# stm32f103c8t6.net
KiCad netlist of a schematic drawn in EasyEDA Pro
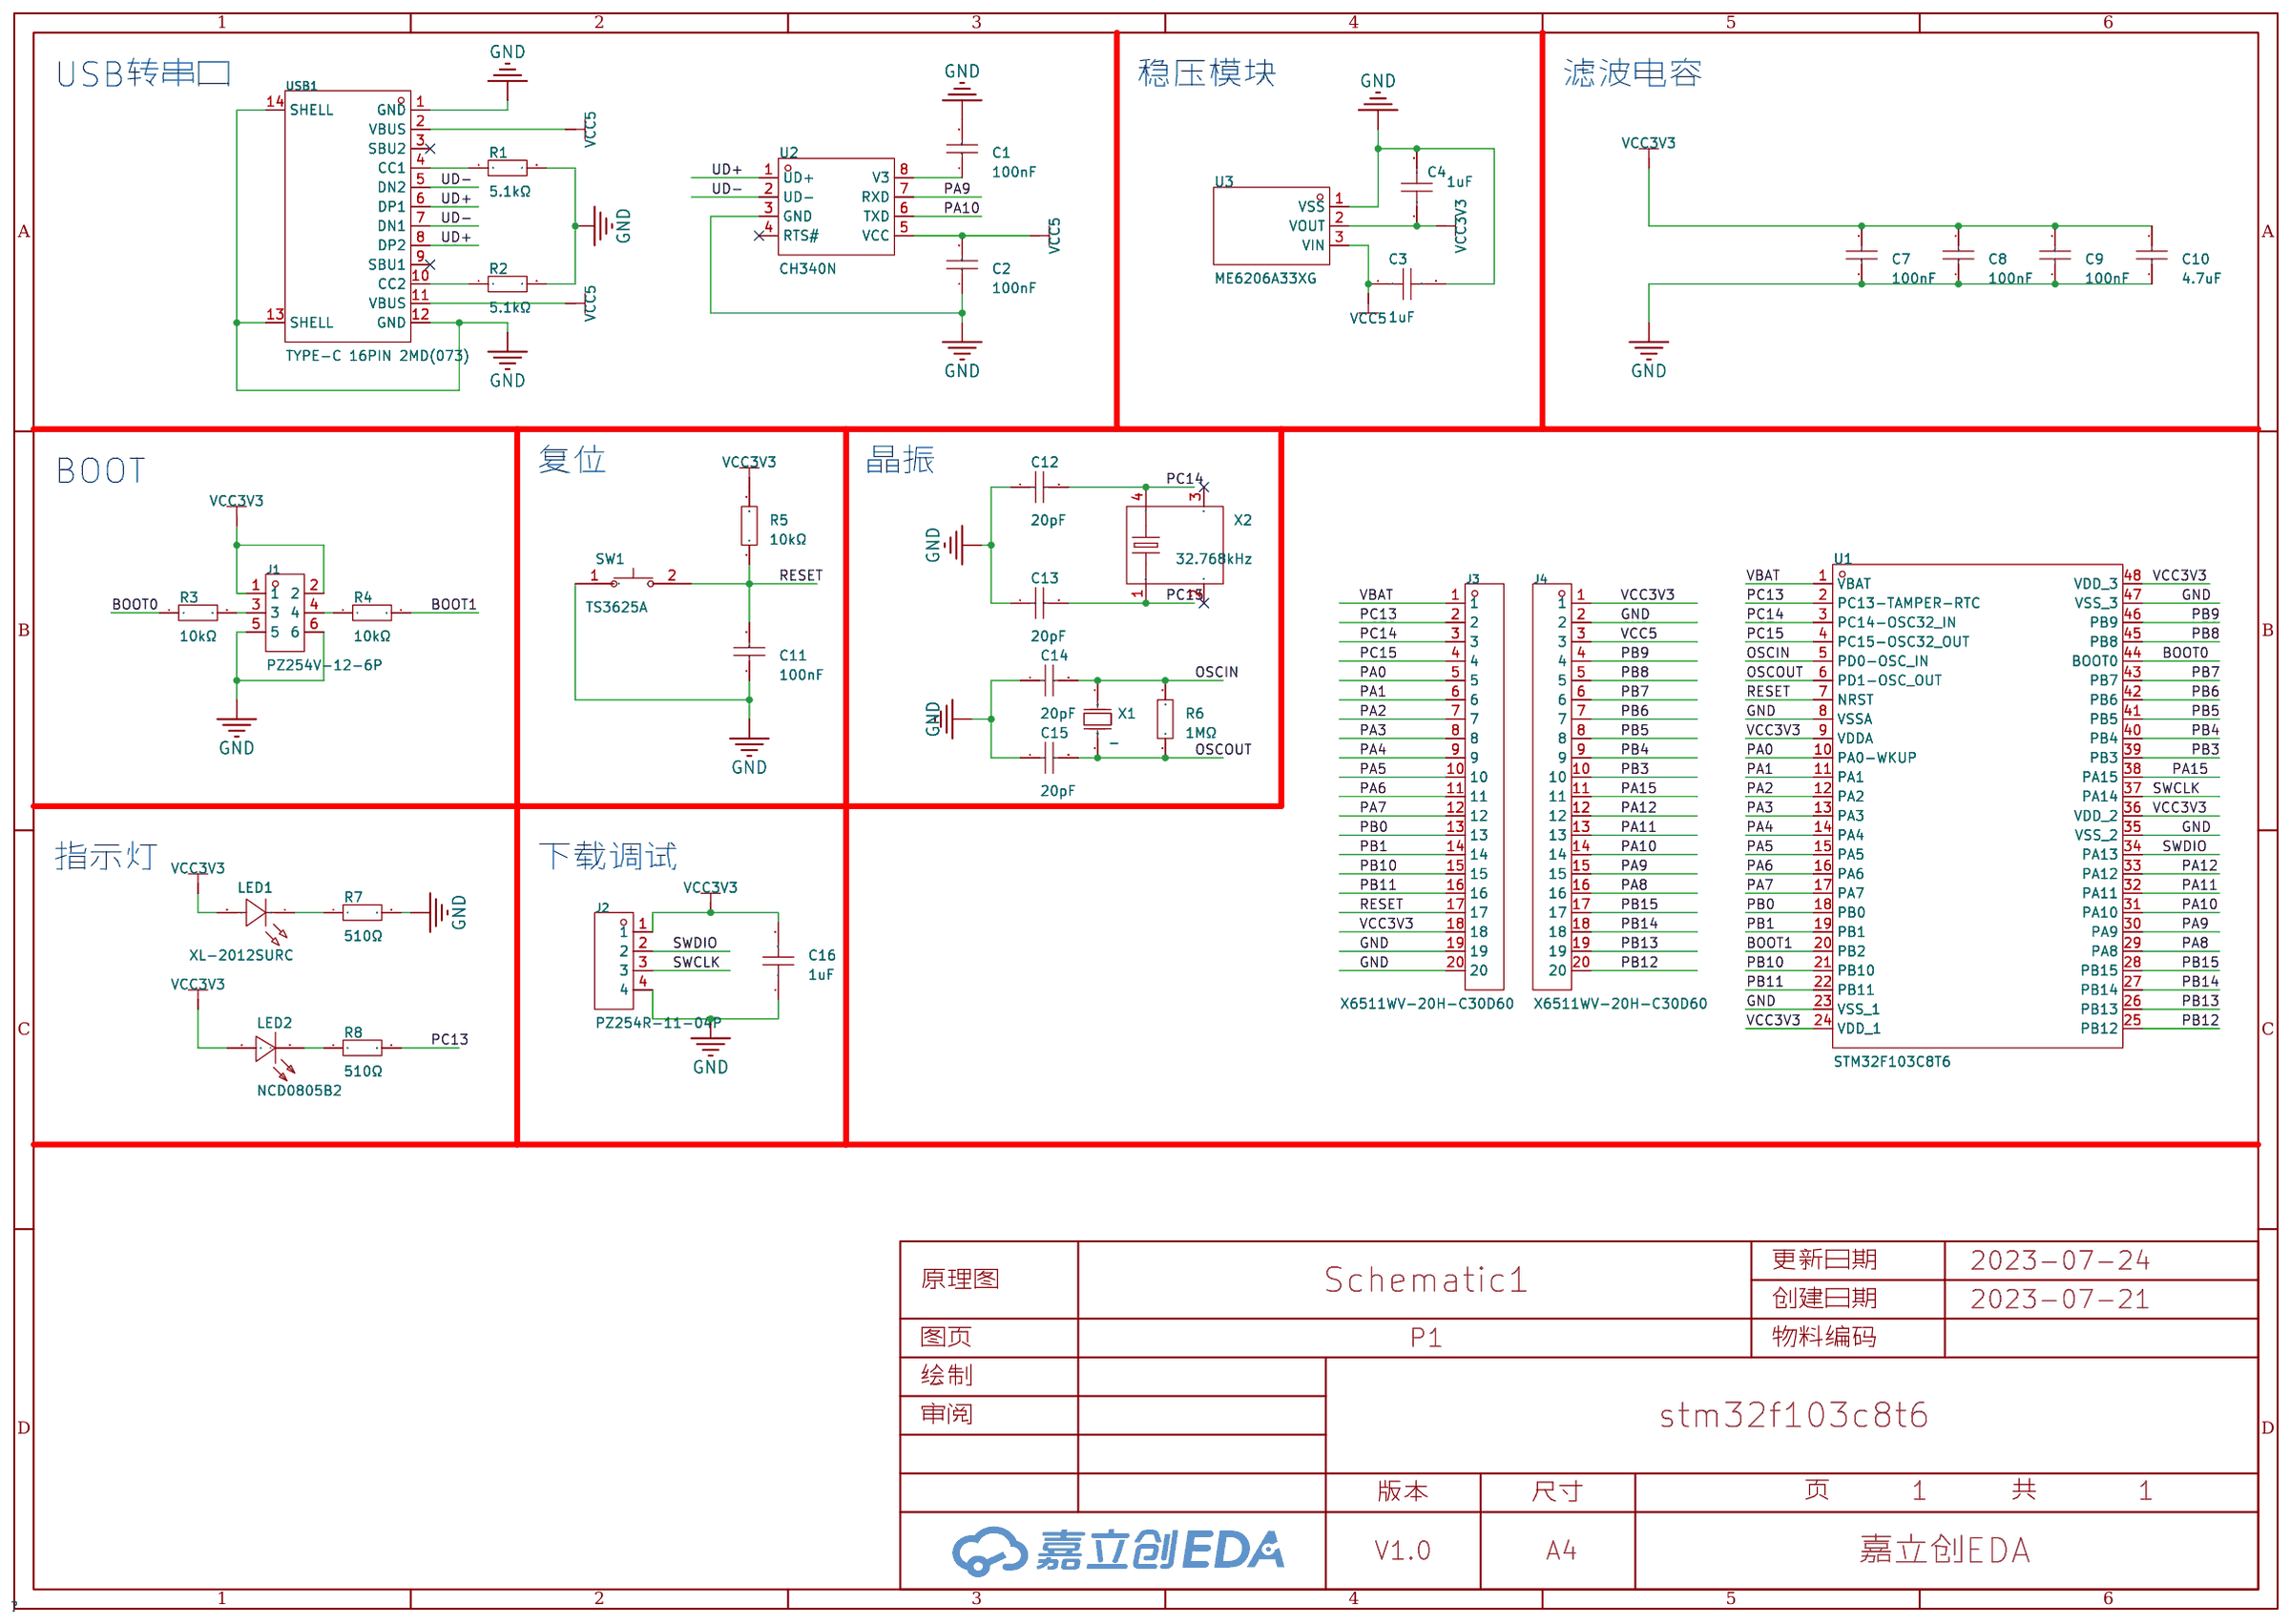
[diagram p0: schematic sheet]

(export (version "E")
  (design (tool "Eeschema 10.0.6"))
  (components
    (comp (ref "C1")
      (value "100nF")
      (footprint "easyedapro:C0603")
      (description "容值:100nF;精度:±10%;额定电压:50V;材质(温度系数):X7R;")
      (fields (field (name "Manufacturer Part") "0603B104K500NT") (field (name "Manufacturer") "FH(风华)"))
      (libsource (lib "easyedapro") (part "0603B104K500NT"))
    )
    (comp (ref "C2")
      (value "100nF")
      (footprint "easyedapro:C0603")
      (description "容值:100nF;精度:±10%;额定电压:50V;材质(温度系数):X7R;")
      (fields (field (name "Manufacturer Part") "0603B104K500NT") (field (name "Manufacturer") "FH(风华)"))
      (libsource (lib "easyedapro") (part "0603B104K500NT"))
    )
    (comp (ref "C3")
      (value "1uF")
      (footprint "easyedapro:C0603")
      (description "温度系数:X7R;精度:±10%;额定电压:50V;容值:1uF;")
      (fields (field (name "Manufacturer Part") "0603B105K500NT") (field (name "Manufacturer") "FH(风华)"))
      (libsource (lib "easyedapro") (part "0603B105K500NT"))
    )
    (comp (ref "C4")
      (value "1uF")
      (footprint "easyedapro:C0603")
      (description "温度系数:X7R;精度:±10%;额定电压:50V;容值:1uF;")
      (fields (field (name "Manufacturer Part") "0603B105K500NT") (field (name "Manufacturer") "FH(风华)"))
      (libsource (lib "easyedapro") (part "0603B105K500NT"))
    )
    (comp (ref "C7")
      (value "100nF")
      (footprint "easyedapro:C0603")
      (description "容值:100nF;精度:±10%;额定电压:50V;材质(温度系数):X7R;")
      (fields (field (name "Manufacturer Part") "0603B104K500NT") (field (name "Manufacturer") "FH(风华)"))
      (libsource (lib "easyedapro") (part "0603B104K500NT"))
    )
    (comp (ref "C8")
      (value "100nF")
      (footprint "easyedapro:C0603")
      (description "容值:100nF;精度:±10%;额定电压:50V;材质(温度系数):X7R;")
      (fields (field (name "Manufacturer Part") "0603B104K500NT") (field (name "Manufacturer") "FH(风华)"))
      (libsource (lib "easyedapro") (part "0603B104K500NT"))
    )
    (comp (ref "C9")
      (value "100nF")
      (footprint "easyedapro:C0603")
      (description "容值:100nF;精度:±10%;额定电压:50V;材质(温度系数):X7R;")
      (fields (field (name "Manufacturer Part") "0603B104K500NT") (field (name "Manufacturer") "FH(风华)"))
      (libsource (lib "easyedapro") (part "0603B104K500NT"))
    )
    (comp (ref "C10")
      (value "4.7uF")
      (footprint "easyedapro:C1206")
      (description "容值:4.7uF;精度:±10%;额定电压:50V;材质(温度系数):X7R;")
      (fields
        (field (name "Manufacturer Part") "CL10A475KO8NNNC")
        (field (name "Manufacturer") "SAMSUNG(三星)")
      )
      (libsource (lib "easyedapro") (part "1206B475K500NT"))
    )
    (comp (ref "C11")
      (value "100nF")
      (footprint "easyedapro:C0603")
      (description "容值:100nF;精度:±10%;额定电压:50V;材质(温度系数):X7R;")
      (fields (field (name "Manufacturer Part") "0603B104K500NT") (field (name "Manufacturer") "FH(风华)"))
      (libsource (lib "easyedapro") (part "0603B104K500NT"))
    )
    (comp (ref "C12")
      (value "20pF")
      (footprint "easyedapro:C0603")
      (description "容值:20pF;精度:±5%;额定电压:50V;材质(温度系数):NP0;")
      (fields
        (field (name "Manufacturer Part") "CC0603JRNPO9BN200")
        (field (name "Manufacturer") "YAGEO(国巨)")
      )
      (libsource (lib "easyedapro") (part "CC0603JRNPO9BN200"))
    )
    (comp (ref "C13")
      (value "20pF")
      (footprint "easyedapro:C0603")
      (description "容值:20pF;精度:±5%;额定电压:50V;材质(温度系数):NP0;")
      (fields
        (field (name "Manufacturer Part") "CC0603JRNPO9BN200")
        (field (name "Manufacturer") "YAGEO(国巨)")
      )
      (libsource (lib "easyedapro") (part "CC0603JRNPO9BN200"))
    )
    (comp (ref "C14")
      (value "20pF")
      (footprint "easyedapro:C0603")
      (description "容值:20pF;精度:±5%;额定电压:50V;材质(温度系数):NP0;")
      (fields
        (field (name "Manufacturer Part") "CC0603JRNPO9BN200")
        (field (name "Manufacturer") "YAGEO(国巨)")
      )
      (libsource (lib "easyedapro") (part "CC0603JRNPO9BN200"))
    )
    (comp (ref "C15")
      (value "20pF")
      (footprint "easyedapro:C0603")
      (description "容值:20pF;精度:±5%;额定电压:50V;材质(温度系数):NP0;")
      (fields
        (field (name "Manufacturer Part") "CC0603JRNPO9BN200")
        (field (name "Manufacturer") "YAGEO(国巨)")
      )
      (libsource (lib "easyedapro") (part "CC0603JRNPO9BN200"))
    )
    (comp (ref "C16")
      (value "1uF")
      (footprint "easyedapro:C0603")
      (description "温度系数:X7R;精度:±10%;额定电压:50V;容值:1uF;")
      (fields (field (name "Manufacturer Part") "0603B105K500NT") (field (name "Manufacturer") "FH(风华)"))
      (libsource (lib "easyedapro") (part "0603B105K500NT"))
    )
    (comp (ref "J1")
      (value "PZ254V-12-6P")
      (footprint "easyedapro:HDR-TH_6P-P2.54-V-M-R2-C3-S2.54")
      (fields (field (name "Manufacturer") "XFCN(兴飞)"))
      (libsource (lib "easyedapro") (part "PZ254V-12-6P"))
    )
    (comp (ref "J2")
      (value "PZ254R-11-04P")
      (footprint "easyedapro:HDR-TH_4P-P2.54-H-M-W10.4")
      (fields (field (name "Manufacturer") "XFCN(兴飞)"))
      (libsource (lib "easyedapro") (part "PZ254R-11-04P"))
    )
    (comp (ref "J3")
      (value "X6511WV-20H-C30D60")
      (footprint "easyedapro:HDR-TH_20P-P2.54-V-M")
      (fields (field (name "Manufacturer") "XKB Connectivity(中国星坤)"))
      (libsource (lib "easyedapro") (part "X6511WV-20H-C30D60"))
    )
    (comp (ref "J4")
      (value "X6511WV-20H-C30D60")
      (footprint "easyedapro:HDR-TH_20P-P2.54-V-M")
      (fields (field (name "Manufacturer") "XKB Connectivity(中国星坤)"))
      (libsource (lib "easyedapro") (part "X6511WV-20H-C30D60"))
    )
    (comp (ref "LED1")
      (value "XL-2012SURC")
      (footprint "easyedapro:LED0805-RD_RED")
      (description "发光颜色:红灯;主波长:617nm~621nm;色温:-;功率:55mW;安装方式:正贴;")
      (fields (field (name "Manufacturer") "XINGLIGHT(成兴光)"))
      (libsource (lib "easyedapro") (part "XL-2012SURC"))
    )
    (comp (ref "LED2")
      (value "NCD0805B2")
      (footprint "easyedapro:LED0805-R-RD")
      (description "发光颜色:蓝灯;")
      (fields (field (name "Manufacturer") "国星光电"))
      (libsource (lib "easyedapro") (part "FC-A2012BK-470H2"))
    )
    (comp (ref "R1")
      (value "5.1kΩ")
      (footprint "easyedapro:R0603")
      (description "电阻类型:厚膜电阻;阻值:5.1kΩ;精度:±1%;功率:100mW;")
      (fields
        (field (name "Manufacturer Part") "0603WAF5101T5E")
        (field (name "Manufacturer") "UNI-ROYAL(厚声)")
      )
      (libsource (lib "easyedapro") (part "0603WAF5101T5E"))
    )
    (comp (ref "R2")
      (value "5.1kΩ")
      (footprint "easyedapro:R0603")
      (description "电阻类型:厚膜电阻;阻值:5.1kΩ;精度:±1%;功率:100mW;")
      (fields
        (field (name "Manufacturer Part") "0603WAF5101T5E")
        (field (name "Manufacturer") "UNI-ROYAL(厚声)")
      )
      (libsource (lib "easyedapro") (part "0603WAF5101T5E"))
    )
    (comp (ref "R3")
      (value "10kΩ")
      (footprint "easyedapro:R0603")
      (description "电阻类型:厚膜电阻;阻值:10kΩ;精度:±1%;功率:100mW;")
      (fields
        (field (name "Manufacturer Part") "0603WAF1002T5E")
        (field (name "Manufacturer") "UNI-ROYAL(厚声)")
      )
      (libsource (lib "easyedapro") (part "0603WAF1002T5E"))
    )
    (comp (ref "R4")
      (value "10kΩ")
      (footprint "easyedapro:R0603")
      (description "电阻类型:厚膜电阻;阻值:10kΩ;精度:±1%;功率:100mW;")
      (fields
        (field (name "Manufacturer Part") "0603WAF1002T5E")
        (field (name "Manufacturer") "UNI-ROYAL(厚声)")
      )
      (libsource (lib "easyedapro") (part "0603WAF1002T5E"))
    )
    (comp (ref "R5")
      (value "10kΩ")
      (footprint "easyedapro:R0603")
      (description "电阻类型:厚膜电阻;阻值:10kΩ;精度:±1%;功率:100mW;")
      (fields
        (field (name "Manufacturer Part") "0603WAF1002T5E")
        (field (name "Manufacturer") "UNI-ROYAL(厚声)")
      )
      (libsource (lib "easyedapro") (part "0603WAF1002T5E"))
    )
    (comp (ref "R6")
      (value "1MΩ")
      (footprint "easyedapro:R0603")
      (description "电阻类型:厚膜电阻;阻值:1MΩ;精度:±1%;功率:100mW;")
      (fields
        (field (name "Manufacturer Part") "0603WAF1004T5E")
        (field (name "Manufacturer") "UNI-ROYAL(厚声)")
      )
      (libsource (lib "easyedapro") (part "0603WAF1004T5E"))
    )
    (comp (ref "R7")
      (value "510Ω")
      (footprint "easyedapro:R0603")
      (description "电阻类型:厚膜电阻;阻值:510Ω;精度:±1%;功率:100mW;")
      (fields
        (field (name "Manufacturer Part") "0603WAF5100T5E")
        (field (name "Manufacturer") "UNI-ROYAL(厚声)")
      )
      (libsource (lib "easyedapro") (part "0603WAF5100T5E"))
    )
    (comp (ref "R8")
      (value "510Ω")
      (footprint "easyedapro:R0603")
      (description "电阻类型:厚膜电阻;阻值:510Ω;精度:±1%;功率:100mW;")
      (fields
        (field (name "Manufacturer Part") "0603WAF5100T5E")
        (field (name "Manufacturer") "UNI-ROYAL(厚声)")
      )
      (libsource (lib "easyedapro") (part "0603WAF5100T5E"))
    )
    (comp (ref "SW1")
      (value "TS3625A")
      (footprint "easyedapro:KEY-SMD_L6.0-W3.5-LS8.4")
      (description "触点电流:50mA;额定电压(DC):12V;电路结构:单刀单掷;安装方式:立贴;带灯:-;作用力:250gf@±50gf;机械寿命:-;")
      (fields (field (name "Manufacturer") "SHOU HAN(首韩)"))
      (libsource (lib "easyedapro") (part "TS3625A"))
    )
    (comp (ref "U1")
      (value "STM32F103C8T6")
      (footprint "easyedapro:LQFP-48_L7.0-W7.0-P0.50-LS9.0-BL")
      (description "CPU内核:ARM Cortex-M3;CPU最大主频:72MHz;程序存储容量:64KB;程序存储器类型:FLASH;RAM总容量:20KB;GPIO端口数量:37;")
      (fields (field (name "Manufacturer") "ST(意法半导体)"))
      (libsource (lib "easyedapro") (part "STM32F103C8T6"))
    )
    (comp (ref "U2")
      (value "CH340N")
      (footprint "easyedapro:SOP-8_L4.9-W3.9-P1.27-LS6.0-BL")
      (fields (field (name "Manufacturer") "WCH(南京沁恒)"))
      (libsource (lib "easyedapro") (part "CH340N_C2977777"))
    )
    (comp (ref "U3")
      (value "ME6206A33XG")
      (footprint "easyedapro:SOT-23-3_L2.9-W1.6-P1.90-LS2.8-BR")
      (description "输出类型:固定;输出极性:正;最大输入电压:6V;输出电压:3.3V;输出电流:300mA;电源纹波抑制比(PSRR):50dB@(1kHz);")
      (fields (field (name "Manufacturer") "MICRONE(南京微盟)"))
      (libsource (lib "easyedapro") (part "ME6206A33XG"))
    )
    (comp (ref "USB1")
      (value "TYPE-C 16PIN 2MD(073)")
      (footprint "easyedapro:USB-C-SMD_TYPE-C-6PIN-2MD-073")
      (description "连接器类型:Type-C;标准:-;公母:母座;触点数量:16;端口数量:1;安装方式:卧贴;额定电流 - 电源:5A;工作温度范围:-25°C~+85°C;")
      (fields (field (name "Manufacturer") "SHOU HAN(首韩)"))
      (libsource (lib "easyedapro") (part "TYPE-C 16PIN 2MD(073)"))
    )
    (comp (ref "X1")
      (value "-")
      (footprint "easyedapro:CRYSTAL-SMD_L11.5-W4.8-LS12.7")
      (description "频率:8MHz;频率公差:±20ppm;负载电容:20pF;")
      (fields
        (field (name "Manufacturer Part") "XIHCELNANF-8MHZ")
        (field (name "Manufacturer") "TAITIEN(泰艺电子)")
      )
      (libsource (lib "easyedapro") (part "X49SM8MSD2SC"))
    )
    (comp (ref "X2")
      (value "32.768kHz")
      (footprint "easyedapro:MC-306_4P-L8.0-W3.2-P5.5-BL")
      (description "频率:32.768kHz;频率公差:±20ppm;负载电容:6pF;")
      (fields (field (name "Manufacturer Part") "Q13MC3062000600") (field (name "Manufacturer") "EPSON(爱普生)"))
      (libsource (lib "easyedapro") (part "MC-306 32.768kHz 6.0pF 20ppm"))
    )
  )
  (nets
    (net (code "1") (name "/BOOT0") (class "Default")
      (node (ref "R3") (pin "1") (pinfunction "1_1") (pintype "input"))
      (node (ref "U1") (pin "44") (pinfunction "BOOT0_44") (pintype "input"))
    )
    (net (code "2") (name "/BOOT1") (class "Default")
      (node (ref "R4") (pin "2") (pinfunction "2_2") (pintype "input"))
      (node (ref "U1") (pin "20") (pinfunction "PB2_20") (pintype "input"))
    )
    (net (code "3") (name "/OSCIN") (class "Default")
      (node (ref "C14") (pin "2") (pinfunction "2_2") (pintype "input"))
      (node (ref "R6") (pin "2") (pinfunction "2_2") (pintype "input"))
      (node (ref "U1") (pin "5") (pinfunction "PD0-OSC_IN_5") (pintype "input"))
      (node (ref "X1") (pin "1") (pinfunction "OSC1_1") (pintype "input"))
    )
    (net (code "4") (name "/OSCOUT") (class "Default")
      (node (ref "C15") (pin "2") (pinfunction "2_2") (pintype "input"))
      (node (ref "R6") (pin "1") (pinfunction "1_1") (pintype "input"))
      (node (ref "U1") (pin "6") (pinfunction "PD1-OSC_OUT_6") (pintype "input"))
      (node (ref "X1") (pin "2") (pinfunction "OSC2_2") (pintype "input"))
    )
    (net (code "5") (name "/PA0") (class "Default")
      (node (ref "J3") (pin "5") (pinfunction "5_5") (pintype "input"))
      (node (ref "U1") (pin "10") (pinfunction "PA0-WKUP_10") (pintype "input"))
    )
    (net (code "6") (name "/PA1") (class "Default")
      (node (ref "J3") (pin "6") (pinfunction "6_6") (pintype "input"))
      (node (ref "U1") (pin "11") (pinfunction "PA1_11") (pintype "input"))
    )
    (net (code "7") (name "/PA2") (class "Default")
      (node (ref "J3") (pin "7") (pinfunction "7_7") (pintype "input"))
      (node (ref "U1") (pin "12") (pinfunction "PA2_12") (pintype "input"))
    )
    (net (code "8") (name "/PA3") (class "Default")
      (node (ref "J3") (pin "8") (pinfunction "8_8") (pintype "input"))
      (node (ref "U1") (pin "13") (pinfunction "PA3_13") (pintype "input"))
    )
    (net (code "9") (name "/PA4") (class "Default")
      (node (ref "J3") (pin "9") (pinfunction "9_9") (pintype "input"))
      (node (ref "U1") (pin "14") (pinfunction "PA4_14") (pintype "input"))
    )
    (net (code "10") (name "/PA5") (class "Default")
      (node (ref "J3") (pin "10") (pinfunction "10_10") (pintype "input"))
      (node (ref "U1") (pin "15") (pinfunction "PA5_15") (pintype "input"))
    )
    (net (code "11") (name "/PA6") (class "Default")
      (node (ref "J3") (pin "11") (pinfunction "11_11") (pintype "input"))
      (node (ref "U1") (pin "16") (pinfunction "PA6_16") (pintype "input"))
    )
    (net (code "12") (name "/PA7") (class "Default")
      (node (ref "J3") (pin "12") (pinfunction "12_12") (pintype "input"))
      (node (ref "U1") (pin "17") (pinfunction "PA7_17") (pintype "input"))
    )
    (net (code "13") (name "/PA8") (class "Default")
      (node (ref "J4") (pin "16") (pinfunction "16_16") (pintype "input"))
      (node (ref "U1") (pin "29") (pinfunction "PA8_29") (pintype "input"))
    )
    (net (code "14") (name "/PA9") (class "Default")
      (node (ref "J4") (pin "15") (pinfunction "15_15") (pintype "input"))
      (node (ref "U1") (pin "30") (pinfunction "PA9_30") (pintype "input"))
      (node (ref "U2") (pin "7") (pinfunction "RXD_7") (pintype "input"))
    )
    (net (code "15") (name "/PA10") (class "Default")
      (node (ref "J4") (pin "14") (pinfunction "14_14") (pintype "input"))
      (node (ref "U1") (pin "31") (pinfunction "PA10_31") (pintype "input"))
      (node (ref "U2") (pin "6") (pinfunction "TXD_6") (pintype "input"))
    )
    (net (code "16") (name "/PA11") (class "Default")
      (node (ref "J4") (pin "13") (pinfunction "13_13") (pintype "input"))
      (node (ref "U1") (pin "32") (pinfunction "PA11_32") (pintype "input"))
    )
    (net (code "17") (name "/PA12") (class "Default")
      (node (ref "J4") (pin "12") (pinfunction "12_12") (pintype "input"))
      (node (ref "U1") (pin "33") (pinfunction "PA12_33") (pintype "input"))
    )
    (net (code "18") (name "/PA15") (class "Default")
      (node (ref "J4") (pin "11") (pinfunction "11_11") (pintype "input"))
      (node (ref "U1") (pin "38") (pinfunction "PA15_38") (pintype "input"))
    )
    (net (code "19") (name "/PB0") (class "Default")
      (node (ref "J3") (pin "13") (pinfunction "13_13") (pintype "input"))
      (node (ref "U1") (pin "18") (pinfunction "PB0_18") (pintype "input"))
    )
    (net (code "20") (name "/PB1") (class "Default")
      (node (ref "J3") (pin "14") (pinfunction "14_14") (pintype "input"))
      (node (ref "U1") (pin "19") (pinfunction "PB1_19") (pintype "input"))
    )
    (net (code "21") (name "/PB3") (class "Default")
      (node (ref "J4") (pin "10") (pinfunction "10_10") (pintype "input"))
      (node (ref "U1") (pin "39") (pinfunction "PB3_39") (pintype "input"))
    )
    (net (code "22") (name "/PB4") (class "Default")
      (node (ref "J4") (pin "9") (pinfunction "9_9") (pintype "input"))
      (node (ref "U1") (pin "40") (pinfunction "PB4_40") (pintype "input"))
    )
    (net (code "23") (name "/PB5") (class "Default")
      (node (ref "J4") (pin "8") (pinfunction "8_8") (pintype "input"))
      (node (ref "U1") (pin "41") (pinfunction "PB5_41") (pintype "input"))
    )
    (net (code "24") (name "/PB6") (class "Default")
      (node (ref "J4") (pin "7") (pinfunction "7_7") (pintype "input"))
      (node (ref "U1") (pin "42") (pinfunction "PB6_42") (pintype "input"))
    )
    (net (code "25") (name "/PB7") (class "Default")
      (node (ref "J4") (pin "6") (pinfunction "6_6") (pintype "input"))
      (node (ref "U1") (pin "43") (pinfunction "PB7_43") (pintype "input"))
    )
    (net (code "26") (name "/PB8") (class "Default")
      (node (ref "J4") (pin "5") (pinfunction "5_5") (pintype "input"))
      (node (ref "U1") (pin "45") (pinfunction "PB8_45") (pintype "input"))
    )
    (net (code "27") (name "/PB9") (class "Default")
      (node (ref "J4") (pin "4") (pinfunction "4_4") (pintype "input"))
      (node (ref "U1") (pin "46") (pinfunction "PB9_46") (pintype "input"))
    )
    (net (code "28") (name "/PB10") (class "Default")
      (node (ref "J3") (pin "15") (pinfunction "15_15") (pintype "input"))
      (node (ref "U1") (pin "21") (pinfunction "PB10_21") (pintype "input"))
    )
    (net (code "29") (name "/PB11") (class "Default")
      (node (ref "J3") (pin "16") (pinfunction "16_16") (pintype "input"))
      (node (ref "U1") (pin "22") (pinfunction "PB11_22") (pintype "input"))
    )
    (net (code "30") (name "/PB12") (class "Default")
      (node (ref "J4") (pin "20") (pinfunction "20_20") (pintype "input"))
      (node (ref "U1") (pin "25") (pinfunction "PB12_25") (pintype "input"))
    )
    (net (code "31") (name "/PB13") (class "Default")
      (node (ref "J4") (pin "19") (pinfunction "19_19") (pintype "input"))
      (node (ref "U1") (pin "26") (pinfunction "PB13_26") (pintype "input"))
    )
    (net (code "32") (name "/PB14") (class "Default")
      (node (ref "J4") (pin "18") (pinfunction "18_18") (pintype "input"))
      (node (ref "U1") (pin "27") (pinfunction "PB14_27") (pintype "input"))
    )
    (net (code "33") (name "/PB15") (class "Default")
      (node (ref "J4") (pin "17") (pinfunction "17_17") (pintype "input"))
      (node (ref "U1") (pin "28") (pinfunction "PB15_28") (pintype "input"))
    )
    (net (code "34") (name "/PC13") (class "Default")
      (node (ref "J3") (pin "2") (pinfunction "2_2") (pintype "input"))
      (node (ref "R8") (pin "2") (pinfunction "2_2") (pintype "input"))
      (node (ref "U1") (pin "2") (pinfunction "PC13-TAMPER-RTC_2") (pintype "input"))
    )
    (net (code "35") (name "/PC14") (class "Default")
      (node (ref "C12") (pin "2") (pinfunction "2_2") (pintype "input"))
      (node (ref "J3") (pin "3") (pinfunction "3_3") (pintype "input"))
      (node (ref "U1") (pin "3") (pinfunction "PC14-OSC32_IN_3") (pintype "input"))
      (node (ref "X2") (pin "4") (pinfunction "4_4") (pintype "input"))
    )
    (net (code "36") (name "/PC15") (class "Default")
      (node (ref "C13") (pin "2") (pinfunction "2_2") (pintype "input"))
      (node (ref "J3") (pin "4") (pinfunction "4_4") (pintype "input"))
      (node (ref "U1") (pin "4") (pinfunction "PC15-OSC32_OUT_4") (pintype "input"))
      (node (ref "X2") (pin "1") (pinfunction "1_1") (pintype "input"))
    )
    (net (code "37") (name "/RESET") (class "Default")
      (node (ref "C11") (pin "2") (pinfunction "2_2") (pintype "input"))
      (node (ref "J3") (pin "17") (pinfunction "17_17") (pintype "input"))
      (node (ref "R5") (pin "1") (pinfunction "1_1") (pintype "input"))
      (node (ref "SW1") (pin "2") (pinfunction "2_2") (pintype "input"))
      (node (ref "U1") (pin "7") (pinfunction "NRST_7") (pintype "input"))
    )
    (net (code "38") (name "/SWCLK") (class "Default")
      (node (ref "J2") (pin "3") (pinfunction "3_3") (pintype "input"))
      (node (ref "U1") (pin "37") (pinfunction "PA14_37") (pintype "input"))
    )
    (net (code "39") (name "/SWDIO") (class "Default")
      (node (ref "J2") (pin "2") (pinfunction "2_2") (pintype "input"))
      (node (ref "U1") (pin "34") (pinfunction "PA13_34") (pintype "input"))
    )
    (net (code "40") (name "/UD+") (class "Default")
      (node (ref "U2") (pin "1") (pinfunction "UD+_1") (pintype "input"))
      (node (ref "USB1") (pin "6") (pinfunction "DP1_6") (pintype "input"))
      (node (ref "USB1") (pin "8") (pinfunction "DP2_8") (pintype "input"))
    )
    (net (code "41") (name "/UD-") (class "Default")
      (node (ref "U2") (pin "2") (pinfunction "UD-_2") (pintype "input"))
      (node (ref "USB1") (pin "5") (pinfunction "DN2_5") (pintype "input"))
      (node (ref "USB1") (pin "7") (pinfunction "DN1_7") (pintype "input"))
    )
    (net (code "42") (name "/VBAT") (class "Default")
      (node (ref "J3") (pin "1") (pinfunction "1_1") (pintype "input"))
      (node (ref "U1") (pin "1") (pinfunction "VBAT_1") (pintype "input"))
    )
    (net (code "43") (name "GND") (class "Default")
      (node (ref "C1") (pin "2") (pinfunction "2_2") (pintype "input"))
      (node (ref "C10") (pin "1") (pinfunction "1_1") (pintype "input"))
      (node (ref "C11") (pin "1") (pinfunction "1_1") (pintype "input"))
      (node (ref "C12") (pin "1") (pinfunction "1_1") (pintype "input"))
      (node (ref "C13") (pin "1") (pinfunction "1_1") (pintype "input"))
      (node (ref "C14") (pin "1") (pinfunction "1_1") (pintype "input"))
      (node (ref "C15") (pin "1") (pinfunction "1_1") (pintype "input"))
      (node (ref "C16") (pin "1") (pinfunction "1_1") (pintype "input"))
      (node (ref "C2") (pin "1") (pinfunction "1_1") (pintype "input"))
      (node (ref "C3") (pin "2") (pinfunction "2_2") (pintype "input"))
      (node (ref "C4") (pin "2") (pinfunction "2_2") (pintype "input"))
      (node (ref "C7") (pin "1") (pinfunction "1_1") (pintype "input"))
      (node (ref "C8") (pin "1") (pinfunction "1_1") (pintype "input"))
      (node (ref "C9") (pin "1") (pinfunction "1_1") (pintype "input"))
      (node (ref "J1") (pin "5") (pinfunction "5_5") (pintype "input"))
      (node (ref "J1") (pin "6") (pinfunction "6_6") (pintype "input"))
      (node (ref "J2") (pin "4") (pinfunction "4_4") (pintype "input"))
      (node (ref "J3") (pin "19") (pinfunction "19_19") (pintype "input"))
      (node (ref "J3") (pin "20") (pinfunction "20_20") (pintype "input"))
      (node (ref "J4") (pin "2") (pinfunction "2_2") (pintype "input"))
      (node (ref "R1") (pin "2") (pinfunction "2_2") (pintype "input"))
      (node (ref "R2") (pin "2") (pinfunction "2_2") (pintype "input"))
      (node (ref "R7") (pin "2") (pinfunction "2_2") (pintype "input"))
      (node (ref "SW1") (pin "1") (pinfunction "1_1") (pintype "input"))
      (node (ref "U1") (pin "23") (pinfunction "VSS_1_23") (pintype "input"))
      (node (ref "U1") (pin "35") (pinfunction "VSS_2_35") (pintype "input"))
      (node (ref "U1") (pin "47") (pinfunction "VSS_3_47") (pintype "input"))
      (node (ref "U1") (pin "8") (pinfunction "VSSA_8") (pintype "input"))
      (node (ref "U2") (pin "3") (pinfunction "GND_3") (pintype "input"))
      (node (ref "U3") (pin "1") (pinfunction "VSS_1") (pintype "input"))
      (node (ref "USB1") (pin "1") (pinfunction "GND_1") (pintype "input"))
      (node (ref "USB1") (pin "12") (pinfunction "GND_12") (pintype "input"))
      (node (ref "USB1") (pin "13") (pinfunction "SHELL_13") (pintype "input"))
      (node (ref "USB1") (pin "14") (pinfunction "SHELL_14") (pintype "input"))
    )
    (net (code "44") (name "Net-(J1-Pad3)") (class "Default")
      (node (ref "J1") (pin "3") (pinfunction "3_3") (pintype "input"))
      (node (ref "R3") (pin "2") (pinfunction "2_2") (pintype "input"))
    )
    (net (code "45") (name "Net-(J1-Pad4)") (class "Default")
      (node (ref "J1") (pin "4") (pinfunction "4_4") (pintype "input"))
      (node (ref "R4") (pin "1") (pinfunction "1_1") (pintype "input"))
    )
    (net (code "46") (name "Net-(LED1-K)") (class "Default")
      (node (ref "LED1") (pin "1") (pinfunction "K_1") (pintype "input"))
      (node (ref "R7") (pin "1") (pinfunction "1_1") (pintype "input"))
    )
    (net (code "47") (name "Net-(LED2--)") (class "Default")
      (node (ref "LED2") (pin "2") (pinfunction "-_2") (pintype "input"))
      (node (ref "R8") (pin "1") (pinfunction "1_1") (pintype "input"))
    )
    (net (code "48") (name "Net-(U2-V3)") (class "Default")
      (node (ref "C1") (pin "1") (pinfunction "1_1") (pintype "input"))
      (node (ref "U2") (pin "8") (pinfunction "V3_8") (pintype "input"))
    )
    (net (code "49") (name "Net-(USB1-CC1)") (class "Default")
      (node (ref "R1") (pin "1") (pinfunction "1_1") (pintype "input"))
      (node (ref "USB1") (pin "4") (pinfunction "CC1_4") (pintype "input"))
    )
    (net (code "50") (name "Net-(USB1-CC2)") (class "Default")
      (node (ref "R2") (pin "1") (pinfunction "1_1") (pintype "input"))
      (node (ref "USB1") (pin "10") (pinfunction "CC2_10") (pintype "input"))
    )
    (net (code "51") (name "VCC3V3") (class "Default")
      (node (ref "C10") (pin "2") (pinfunction "2_2") (pintype "input"))
      (node (ref "C16") (pin "2") (pinfunction "2_2") (pintype "input"))
      (node (ref "C4") (pin "1") (pinfunction "1_1") (pintype "input"))
      (node (ref "C7") (pin "2") (pinfunction "2_2") (pintype "input"))
      (node (ref "C8") (pin "2") (pinfunction "2_2") (pintype "input"))
      (node (ref "C9") (pin "2") (pinfunction "2_2") (pintype "input"))
      (node (ref "J1") (pin "1") (pinfunction "1_1") (pintype "input"))
      (node (ref "J1") (pin "2") (pinfunction "2_2") (pintype "input"))
      (node (ref "J2") (pin "1") (pinfunction "1_1") (pintype "input"))
      (node (ref "J3") (pin "18") (pinfunction "18_18") (pintype "input"))
      (node (ref "J4") (pin "1") (pinfunction "1_1") (pintype "input"))
      (node (ref "LED1") (pin "2") (pinfunction "A_2") (pintype "input"))
      (node (ref "LED2") (pin "1") (pinfunction "+_1") (pintype "input"))
      (node (ref "R5") (pin "2") (pinfunction "2_2") (pintype "input"))
      (node (ref "U1") (pin "24") (pinfunction "VDD_1_24") (pintype "input"))
      (node (ref "U1") (pin "36") (pinfunction "VDD_2_36") (pintype "input"))
      (node (ref "U1") (pin "48") (pinfunction "VDD_3_48") (pintype "input"))
      (node (ref "U1") (pin "9") (pinfunction "VDDA_9") (pintype "input"))
      (node (ref "U3") (pin "2") (pinfunction "VOUT_2") (pintype "input"))
    )
    (net (code "52") (name "VCC5") (class "Default")
      (node (ref "C2") (pin "2") (pinfunction "2_2") (pintype "input"))
      (node (ref "C3") (pin "1") (pinfunction "1_1") (pintype "input"))
      (node (ref "J4") (pin "3") (pinfunction "3_3") (pintype "input"))
      (node (ref "U2") (pin "5") (pinfunction "VCC_5") (pintype "input"))
      (node (ref "U3") (pin "3") (pinfunction "VIN_3") (pintype "input"))
      (node (ref "USB1") (pin "11") (pinfunction "VBUS_11") (pintype "input"))
      (node (ref "USB1") (pin "2") (pinfunction "VBUS_2") (pintype "input"))
    )
    (net (code "53") (name "unconnected-(U2-RTS#-Pad4)") (class "Default")
      (node (ref "U2") (pin "4") (pinfunction "RTS#_4") (pintype "input+no_connect"))
    )
    (net (code "54") (name "unconnected-(USB1-SBU1-Pad9)") (class "Default")
      (node (ref "USB1") (pin "9") (pinfunction "SBU1_9") (pintype "input+no_connect"))
    )
    (net (code "55") (name "unconnected-(USB1-SBU2-Pad3)") (class "Default")
      (node (ref "USB1") (pin "3") (pinfunction "SBU2_3") (pintype "input+no_connect"))
    )
    (net (code "56") (name "unconnected-(X2-Pad2)") (class "Default")
      (node (ref "X2") (pin "2") (pinfunction "2_2") (pintype "input+no_connect"))
    )
    (net (code "57") (name "unconnected-(X2-Pad3)") (class "Default")
      (node (ref "X2") (pin "3") (pinfunction "3_3") (pintype "input+no_connect"))
    )
  )
)
